# SCHEMA_EASYEDA.net
KiCad netlist of a schematic drawn in EasyEDA
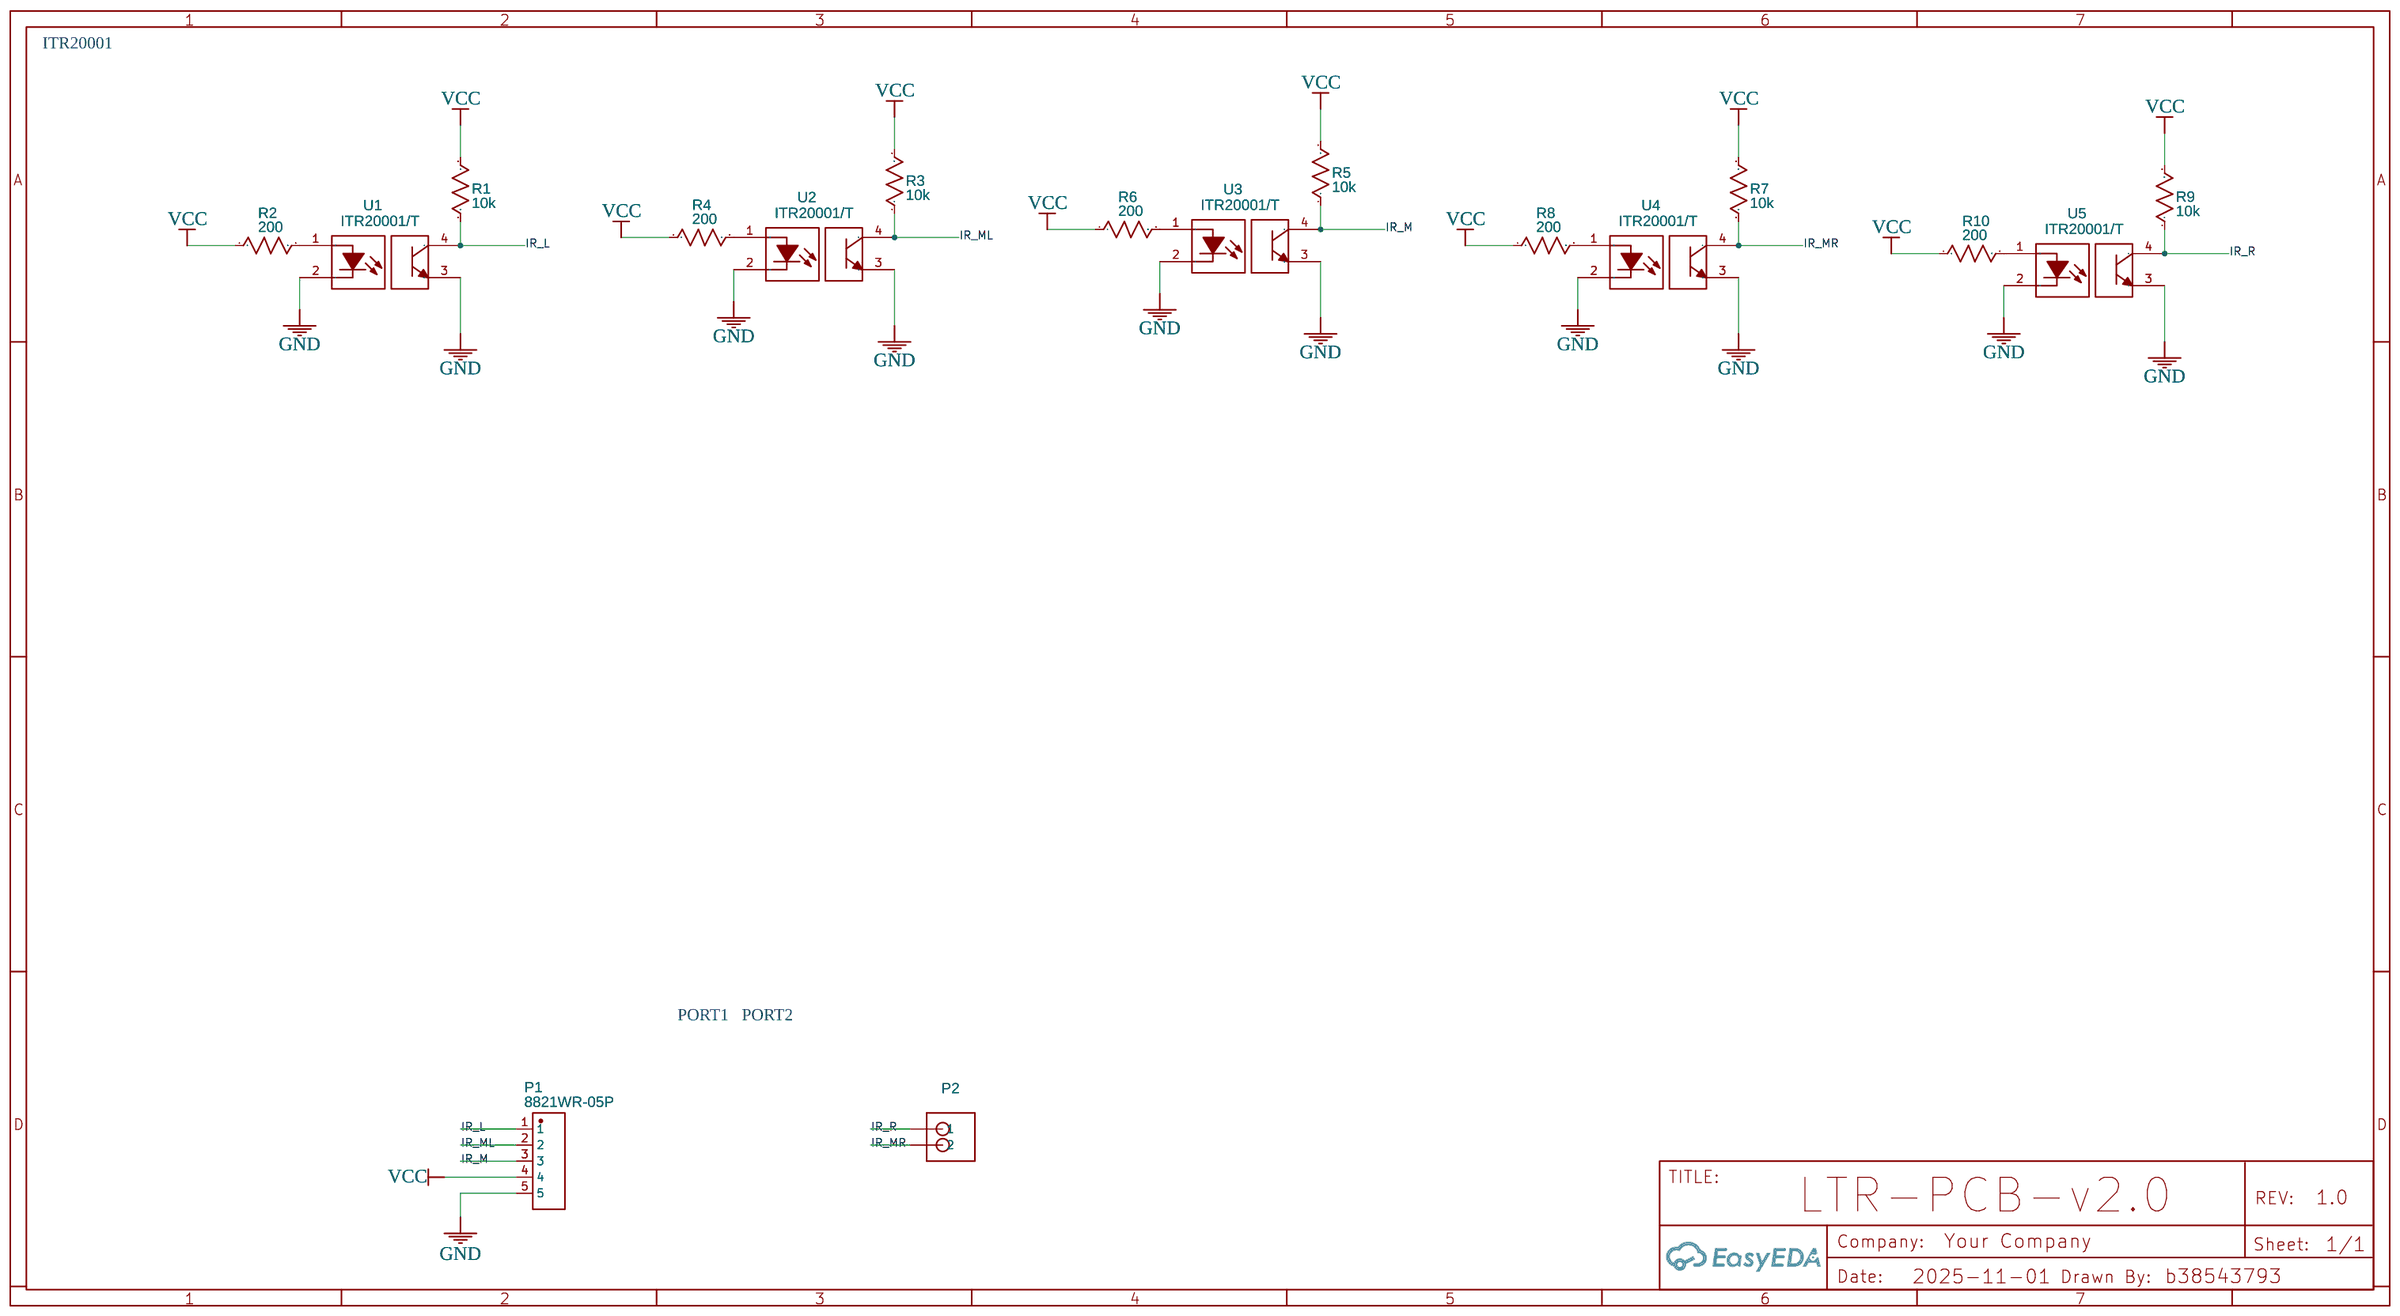
[diagram p0: schematic sheet]

(export (version "E")
  (design (tool "Eeschema 10.0.6"))
  (components
    (comp (ref "P1")
      (value "8821WR-05P")
      (fields (field (name "Manufacturer") "HanElectricity(瀚源)"))
      (libsource (lib "") (part "8821WR-05P"))
    )
    (comp (ref "P2") (value "JST-PH_2-PIN_HEADER") (libsource (lib "") (part "JST-PH_2-PIN_HEADER")))
    (comp (ref "R1") (value "10k") (libsource (lib "") (part "R_0603_US_1")))
    (comp (ref "R2") (value "200") (libsource (lib "") (part "R_0603_US")))
    (comp (ref "R3") (value "10k") (libsource (lib "") (part "R_0603_US_1")))
    (comp (ref "R4") (value "200") (libsource (lib "") (part "R_0603_US")))
    (comp (ref "R5") (value "10k") (libsource (lib "") (part "R_0603_US_1")))
    (comp (ref "R6") (value "200") (libsource (lib "") (part "R_0603_US")))
    (comp (ref "R7") (value "10k") (libsource (lib "") (part "R_0603_US_1")))
    (comp (ref "R8") (value "200") (libsource (lib "") (part "R_0603_US")))
    (comp (ref "R9") (value "10k") (libsource (lib "") (part "R_0603_US_1")))
    (comp (ref "R10") (value "200") (libsource (lib "") (part "R_0603_US")))
    (comp (ref "U1")
      (value "ITR20001/T")
      (fields (field (name "Manufacturer") "EVERLIGHT(亿光)"))
      (libsource (lib "") (part "ITR20001/T"))
    )
    (comp (ref "U2")
      (value "ITR20001/T")
      (fields (field (name "Manufacturer") "EVERLIGHT(亿光)"))
      (libsource (lib "") (part "ITR20001/T"))
    )
    (comp (ref "U3")
      (value "ITR20001/T")
      (fields (field (name "Manufacturer") "EVERLIGHT(亿光)"))
      (libsource (lib "") (part "ITR20001/T"))
    )
    (comp (ref "U4")
      (value "ITR20001/T")
      (fields (field (name "Manufacturer") "EVERLIGHT(亿光)"))
      (libsource (lib "") (part "ITR20001/T"))
    )
    (comp (ref "U5")
      (value "ITR20001/T")
      (fields (field (name "Manufacturer") "EVERLIGHT(亿光)"))
      (libsource (lib "") (part "ITR20001/T"))
    )
  )
  (nets
    (net (code "1") (name "/IR_L") (class "Default")
      (node (ref "P1") (pin "1") (pinfunction "1_1") (pintype "unspecified"))
      (node (ref "R1") (pin "1") (pinfunction "1_1") (pintype "unspecified"))
      (node (ref "U1") (pin "4") (pinfunction "4_4") (pintype "unspecified"))
    )
    (net (code "2") (name "/IR_M") (class "Default")
      (node (ref "P1") (pin "3") (pinfunction "3_3") (pintype "unspecified"))
      (node (ref "R5") (pin "1") (pinfunction "1_1") (pintype "unspecified"))
      (node (ref "U3") (pin "4") (pinfunction "4_4") (pintype "unspecified"))
    )
    (net (code "3") (name "/IR_ML") (class "Default")
      (node (ref "P1") (pin "2") (pinfunction "2_2") (pintype "unspecified"))
      (node (ref "R3") (pin "1") (pinfunction "1_1") (pintype "unspecified"))
      (node (ref "U2") (pin "4") (pinfunction "4_4") (pintype "unspecified"))
    )
    (net (code "4") (name "/IR_MR") (class "Default")
      (node (ref "P2") (pin "P2") (pinfunction "2_P2") (pintype "unspecified"))
      (node (ref "R7") (pin "1") (pinfunction "1_1") (pintype "unspecified"))
      (node (ref "U4") (pin "4") (pinfunction "4_4") (pintype "unspecified"))
    )
    (net (code "5") (name "/IR_R") (class "Default")
      (node (ref "P2") (pin "P1") (pinfunction "1_P1") (pintype "unspecified"))
      (node (ref "R9") (pin "1") (pinfunction "1_1") (pintype "unspecified"))
      (node (ref "U5") (pin "4") (pinfunction "4_4") (pintype "unspecified"))
    )
    (net (code "6") (name "GND") (class "Default")
      (node (ref "P1") (pin "5") (pinfunction "5_5") (pintype "unspecified"))
      (node (ref "U1") (pin "2") (pinfunction "2_2") (pintype "unspecified"))
      (node (ref "U1") (pin "3") (pinfunction "3_3") (pintype "unspecified"))
      (node (ref "U2") (pin "2") (pinfunction "2_2") (pintype "unspecified"))
      (node (ref "U2") (pin "3") (pinfunction "3_3") (pintype "unspecified"))
      (node (ref "U3") (pin "2") (pinfunction "2_2") (pintype "unspecified"))
      (node (ref "U3") (pin "3") (pinfunction "3_3") (pintype "unspecified"))
      (node (ref "U4") (pin "2") (pinfunction "2_2") (pintype "unspecified"))
      (node (ref "U4") (pin "3") (pinfunction "3_3") (pintype "unspecified"))
      (node (ref "U5") (pin "2") (pinfunction "2_2") (pintype "unspecified"))
      (node (ref "U5") (pin "3") (pinfunction "3_3") (pintype "unspecified"))
    )
    (net (code "7") (name "Net-(R2-Pad2)") (class "Default")
      (node (ref "R2") (pin "2") (pinfunction "2_2") (pintype "unspecified"))
      (node (ref "U1") (pin "1") (pinfunction "1_1") (pintype "unspecified"))
    )
    (net (code "8") (name "Net-(R4-Pad2)") (class "Default")
      (node (ref "R4") (pin "2") (pinfunction "2_2") (pintype "unspecified"))
      (node (ref "U2") (pin "1") (pinfunction "1_1") (pintype "unspecified"))
    )
    (net (code "9") (name "Net-(R6-Pad2)") (class "Default")
      (node (ref "R6") (pin "2") (pinfunction "2_2") (pintype "unspecified"))
      (node (ref "U3") (pin "1") (pinfunction "1_1") (pintype "unspecified"))
    )
    (net (code "10") (name "Net-(R8-Pad2)") (class "Default")
      (node (ref "R8") (pin "2") (pinfunction "2_2") (pintype "unspecified"))
      (node (ref "U4") (pin "1") (pinfunction "1_1") (pintype "unspecified"))
    )
    (net (code "11") (name "Net-(R10-Pad2)") (class "Default")
      (node (ref "R10") (pin "2") (pinfunction "2_2") (pintype "unspecified"))
      (node (ref "U5") (pin "1") (pinfunction "1_1") (pintype "unspecified"))
    )
    (net (code "12") (name "VCC") (class "Default")
      (node (ref "P1") (pin "4") (pinfunction "4_4") (pintype "unspecified"))
      (node (ref "R1") (pin "2") (pinfunction "2_2") (pintype "unspecified"))
      (node (ref "R10") (pin "1") (pinfunction "1_1") (pintype "unspecified"))
      (node (ref "R2") (pin "1") (pinfunction "1_1") (pintype "unspecified"))
      (node (ref "R3") (pin "2") (pinfunction "2_2") (pintype "unspecified"))
      (node (ref "R4") (pin "1") (pinfunction "1_1") (pintype "unspecified"))
      (node (ref "R5") (pin "2") (pinfunction "2_2") (pintype "unspecified"))
      (node (ref "R6") (pin "1") (pinfunction "1_1") (pintype "unspecified"))
      (node (ref "R7") (pin "2") (pinfunction "2_2") (pintype "unspecified"))
      (node (ref "R8") (pin "1") (pinfunction "1_1") (pintype "unspecified"))
      (node (ref "R9") (pin "2") (pinfunction "2_2") (pintype "unspecified"))
    )
  )
)
